# Digital_and_PS.net
KiCad netlist of a schematic drawn in Altium Designer
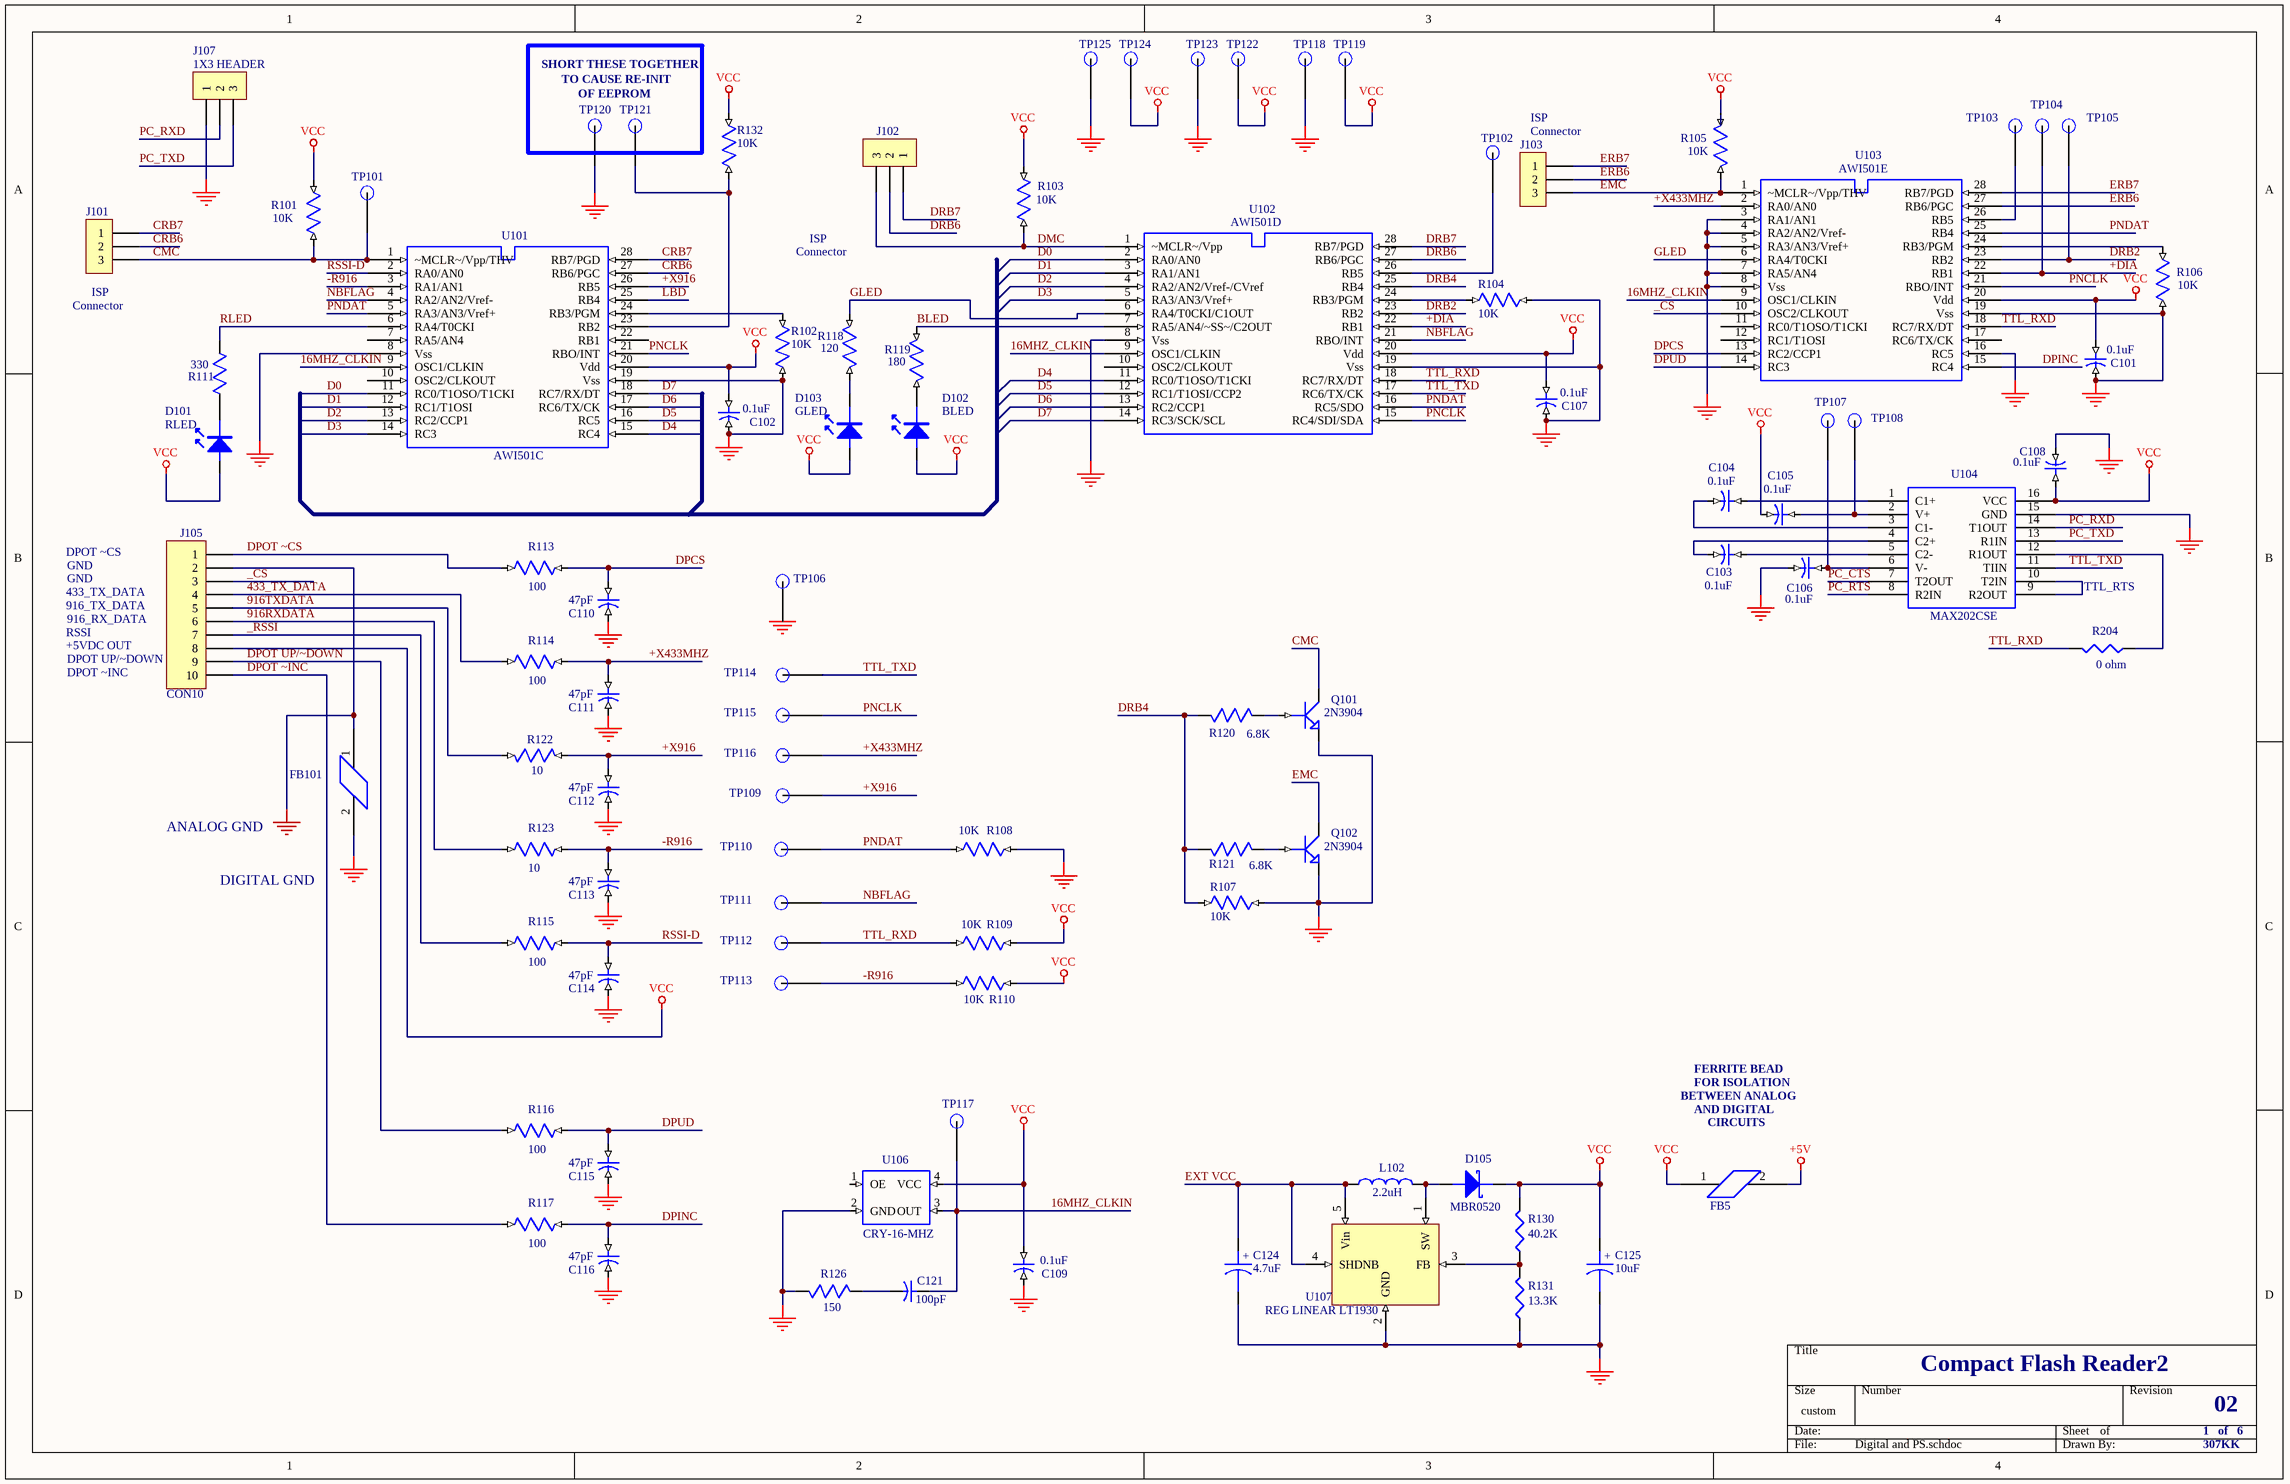
[diagram p0: Digital and PS.schdoc]

(export (version "E")
  (design (tool "Eeschema 10.0.6"))
  (components
    (comp (ref "C101") (value "0.1uF") (footprint "0603") (libsource (lib "*") (part "C_603")))
    (comp (ref "C102") (value "0.1uF") (footprint "0603") (libsource (lib "*") (part "C_603")))
    (comp (ref "C103") (value "0.1uF") (footprint "0603") (libsource (lib "") (part "C_603_1")))
    (comp (ref "C104") (value "0.1uF") (footprint "0603") (libsource (lib "") (part "C_603_1")))
    (comp (ref "C105") (value "0.1uF") (footprint "0603") (libsource (lib "") (part "C_603_1")))
    (comp (ref "C106") (value "0.1uF") (footprint "0603") (libsource (lib "") (part "C_603_1")))
    (comp (ref "C107") (value "0.1uF") (footprint "0603") (libsource (lib "*") (part "C_603")))
    (comp (ref "C108") (value "0.1uF") (footprint "0603") (libsource (lib "") (part "C_603_1")))
    (comp (ref "C109") (value "0.1uF") (footprint "0603") (libsource (lib "") (part "C_603_1")))
    (comp (ref "C110") (value "47pF") (footprint "0603") (libsource (lib "*") (part "C0603")))
    (comp (ref "C111") (value "47pF") (footprint "0603") (libsource (lib "*") (part "C0603")))
    (comp (ref "C112") (value "47pF") (footprint "0603") (libsource (lib "*") (part "C0603")))
    (comp (ref "C113") (value "47pF") (footprint "0603") (libsource (lib "*") (part "C0603")))
    (comp (ref "C114") (value "47pF") (footprint "0603") (libsource (lib "*") (part "C0603")))
    (comp (ref "C115") (value "47pF") (footprint "0603") (libsource (lib "*") (part "C0603")))
    (comp (ref "C116") (value "47pF") (footprint "0603") (libsource (lib "*") (part "C0603")))
    (comp (ref "C121") (value "100pF") (footprint "0603") (libsource (lib "*") (part "C_0603")))
    (comp (ref "C124")
      (value "4.7uF")
      (footprint "CAP A CASE")
      (description "Capacitor")
      (libsource (lib "*") (part "CAPACITOR POL"))
    )
    (comp (ref "C125")
      (value "10uF")
      (footprint "CAP A CASE")
      (description "Capacitor")
      (libsource (lib "*") (part "CAPACITOR POL"))
    )
    (comp (ref "D101") (value "RLED") (footprint "SOD123 DIODE") (libsource (lib "*") (part "LED")))
    (comp (ref "D102") (value "BLED") (footprint "SOD123 DIODE") (libsource (lib "*") (part "LED")))
    (comp (ref "D103") (value "GLED") (footprint "SOD123 DIODE") (libsource (lib "*") (part "LED")))
    (comp (ref "D105")
      (value "MBR0520")
      (footprint "SOD123")
      (description "Schottky Diode")
      (libsource (lib "*") (part "DIODE SCHOTTKY"))
    )
    (comp (ref "FB5") (value "FB") (footprint "0603") (libsource (lib "*") (part "FB_0603")))
    (comp (ref "FB101") (value "FB") (footprint "0603") (libsource (lib "*") (part "FB_0603")))
    (comp (ref "J101")
      (value "1X3 HEADER")
      (footprint "1X3 HEADER")
      (description "Connector")
      (libsource (lib "") (part "CON3_1"))
    )
    (comp (ref "J102")
      (value "1X3 HEADER")
      (footprint "1X3 HEADER")
      (description "Connector")
      (libsource (lib "*") (part "CON3"))
    )
    (comp (ref "J103")
      (value "1X3 HEADER")
      (footprint "1X3 HEADER")
      (description "Connector")
      (libsource (lib "") (part "CON3_1"))
    )
    (comp (ref "J105")
      (value "CON10")
      (footprint "1X10 HEADER SPECIAL")
      (description "Connector")
      (libsource (lib "*") (part "CON10"))
    )
    (comp (ref "J107")
      (value "1X3 HEADER")
      (footprint "1X3 HEADER")
      (description "Connector")
      (libsource (lib "") (part "CON3_2"))
    )
    (comp (ref "L102")
      (value "2.2uH")
      (footprint "COIL BOURNS SDR7030-330M")
      (libsource (lib "*") (part "INDUCTOR1"))
    )
    (comp (ref "Q101")
      (value "2N3904")
      (footprint "SOT23 TRANS")
      (description "NPN Transistor")
      (libsource (lib "*") (part "NPN1"))
    )
    (comp (ref "Q102")
      (value "2N3904")
      (footprint "SOT23 TRANS")
      (description "NPN Transistor")
      (libsource (lib "*") (part "NPN1"))
    )
    (comp (ref "R101") (value "10K") (footprint "0603") (libsource (lib "*") (part "R_603")))
    (comp (ref "R102") (value "10K") (footprint "0603") (libsource (lib "*") (part "R_603")))
    (comp (ref "R103") (value "10K") (footprint "0603") (libsource (lib "*") (part "R_603")))
    (comp (ref "R104") (value "10K") (footprint "0603") (libsource (lib "*") (part "R_603")))
    (comp (ref "R105") (value "10K") (footprint "0603") (libsource (lib "*") (part "R_603")))
    (comp (ref "R106") (value "10K") (footprint "0603") (libsource (lib "*") (part "R_603")))
    (comp (ref "R107") (value "10K") (footprint "0603") (libsource (lib "*") (part "R_603")))
    (comp (ref "R108") (value "10K") (footprint "0603") (libsource (lib "*") (part "R_603")))
    (comp (ref "R109") (value "10K") (footprint "0603") (libsource (lib "*") (part "R_603")))
    (comp (ref "R110") (value "10K") (footprint "0603") (libsource (lib "*") (part "R_603")))
    (comp (ref "R111") (value "330") (footprint "0603") (libsource (lib "*") (part "R_0603")))
    (comp (ref "R113") (value "100") (footprint "0603") (libsource (lib "*") (part "R0603")))
    (comp (ref "R114") (value "100") (footprint "0603") (libsource (lib "*") (part "R0603")))
    (comp (ref "R115") (value "100") (footprint "0603") (libsource (lib "*") (part "R0603")))
    (comp (ref "R116") (value "100") (footprint "0603") (libsource (lib "*") (part "R0603")))
    (comp (ref "R117") (value "100") (footprint "0603") (libsource (lib "*") (part "R0603")))
    (comp (ref "R118") (value "120") (footprint "0603") (libsource (lib "*") (part "R0402")))
    (comp (ref "R119") (value "180") (footprint "0603") (libsource (lib "*") (part "R0402")))
    (comp (ref "R120") (value "6.8K") (footprint "0603") (libsource (lib "*") (part "R_0603")))
    (comp (ref "R121") (value "6.8K") (footprint "0603") (libsource (lib "*") (part "R_0603")))
    (comp (ref "R122") (value "10") (footprint "0603") (libsource (lib "*") (part "R_603")))
    (comp (ref "R123") (value "10") (footprint "0603") (libsource (lib "*") (part "R0603")))
    (comp (ref "R126") (value "150") (footprint "0603") (libsource (lib "*") (part "R_0603")))
    (comp (ref "R130") (value "40.2K") (footprint "0603") (libsource (lib "*") (part "RES1")))
    (comp (ref "R131") (value "13.3K") (footprint "0603") (libsource (lib "*") (part "RES1")))
    (comp (ref "R132") (value "10K") (footprint "0603") (libsource (lib "*") (part "R_603")))
    (comp (ref "R204") (value "0 ohm") (footprint "0603") (libsource (lib "*") (part "RES1")))
    (comp (ref "TP101") (value "TP") (footprint "TEST POINT PAD") (libsource (lib "*") (part "TESTPOINT_1")))
    (comp (ref "TP102") (value "TP") (footprint "TEST POINT PAD") (libsource (lib "*") (part "TESTPOINT_1")))
    (comp (ref "TP103") (value "TP") (footprint "TEST POINT PAD") (libsource (lib "*") (part "TESTPOINT_1")))
    (comp (ref "TP104") (value "TP") (footprint "TEST POINT PAD") (libsource (lib "*") (part "TESTPOINT_1")))
    (comp (ref "TP105") (value "TP") (footprint "TEST POINT PAD") (libsource (lib "*") (part "TESTPOINT_1")))
    (comp (ref "TP106") (value "TP") (footprint "TEST POINT PAD") (libsource (lib "*") (part "TESTPOINT_1")))
    (comp (ref "TP107") (value "TP") (footprint "TEST POINT PAD") (libsource (lib "*") (part "TESTPOINT_1")))
    (comp (ref "TP108") (value "TP") (footprint "TEST POINT PAD") (libsource (lib "*") (part "TESTPOINT_1")))
    (comp (ref "TP109") (value "TP") (footprint "TEST POINT PAD") (libsource (lib "*") (part "TESTPOINT_1")))
    (comp (ref "TP110") (value "TP") (footprint "TEST POINT PAD") (libsource (lib "*") (part "TESTPOINT_1")))
    (comp (ref "TP111") (value "TP") (footprint "TEST POINT PAD") (libsource (lib "*") (part "TESTPOINT_1")))
    (comp (ref "TP112") (value "TP") (footprint "TEST POINT PAD") (libsource (lib "*") (part "TESTPOINT_1")))
    (comp (ref "TP113") (value "TP") (footprint "TEST POINT PAD") (libsource (lib "*") (part "TESTPOINT_1")))
    (comp (ref "TP114") (value "TP") (footprint "TEST POINT PAD") (libsource (lib "*") (part "TESTPOINT_1")))
    (comp (ref "TP115") (value "TP") (footprint "TEST POINT PAD") (libsource (lib "*") (part "TESTPOINT_1")))
    (comp (ref "TP116") (value "TP") (footprint "TEST POINT PAD") (libsource (lib "*") (part "TESTPOINT_1")))
    (comp (ref "TP117") (value "TP") (footprint "TEST POINT PAD") (libsource (lib "*") (part "TESTPOINT_1")))
    (comp (ref "TP118") (value "TP") (footprint "TEST POINT PAD") (libsource (lib "*") (part "TESTPOINT_1")))
    (comp (ref "TP119") (value "TP") (footprint "TEST POINT PAD") (libsource (lib "*") (part "TESTPOINT_1")))
    (comp (ref "TP120") (value "TP") (footprint "TEST POINT PAD") (libsource (lib "*") (part "TESTPOINT_1")))
    (comp (ref "TP121") (value "TP") (footprint "TEST POINT PAD") (libsource (lib "*") (part "TESTPOINT_1")))
    (comp (ref "TP122") (value "TP") (footprint "TEST POINT PAD") (libsource (lib "*") (part "TESTPOINT_1")))
    (comp (ref "TP123") (value "TP") (footprint "TEST POINT PAD") (libsource (lib "*") (part "TESTPOINT_1")))
    (comp (ref "TP124") (value "TP") (footprint "TEST POINT PAD") (libsource (lib "*") (part "TESTPOINT_1")))
    (comp (ref "TP125") (value "TP") (footprint "TEST POINT PAD") (libsource (lib "*") (part "TESTPOINT_1")))
    (comp (ref "U101") (value "AWI501C") (footprint "SSOP28") (libsource (lib "*") (part "PIC16F870")))
    (comp (ref "U102") (value "AWI501D") (footprint "SSOP28") (libsource (lib "*") (part "PIC16F876A")))
    (comp (ref "U103") (value "AWI501E") (footprint "SSOP28") (libsource (lib "*") (part "PIC16F870")))
    (comp (ref "U104") (value "MAX202CSE") (footprint "SO16") (libsource (lib "*") (part "MAX202CSE")))
    (comp (ref "U106")
      (value "CRY-16-MHZ")
      (footprint "SMT OSCILLATOR")
      (libsource (lib "*") (part "CRY-SMD-5-7"))
    )
    (comp (ref "U107")
      (value "REG LINEAR LT1930")
      (footprint "SOT23-5A")
      (libsource (lib "*") (part "REG LINEAR LT1930"))
    )
  )
  (nets
    (net (code "1") (name "+5V") (class "Default")
      (node (ref "FB5") (pin "2") (pinfunction "1_2") (pintype "passive"))
    )
    (net (code "2") (name "/+DIA") (class "Default")
      (node (ref "TP104") (pin "1") (pinfunction "TP_1") (pintype "passive"))
      (node (ref "U102") (pin "22") (pinfunction "RB1_22") (pintype "input"))
      (node (ref "U103") (pin "22") (pinfunction "RB1_22") (pintype "input"))
    )
    (net (code "3") (name "/+X433MHZ") (class "Default")
      (node (ref "C111") (pin "1") (pinfunction "A_1") (pintype "input"))
      (node (ref "R114") (pin "2") (pinfunction "B_2") (pintype "input"))
      (node (ref "TP116") (pin "1") (pinfunction "TP_1") (pintype "passive"))
      (node (ref "U103") (pin "2") (pinfunction "RA0/AN0_2") (pintype "input"))
    )
    (net (code "4") (name "/+X916") (class "Default")
      (node (ref "C112") (pin "1") (pinfunction "A_1") (pintype "input"))
      (node (ref "R122") (pin "1") (pinfunction "A_1") (pintype "input"))
      (node (ref "TP109") (pin "1") (pinfunction "TP_1") (pintype "passive"))
      (node (ref "U101") (pin "26") (pinfunction "RB5_26") (pintype "input"))
    )
    (net (code "5") (name "/-R916") (class "Default")
      (node (ref "C113") (pin "1") (pinfunction "A_1") (pintype "input"))
      (node (ref "R110") (pin "2") (pinfunction "B_2") (pintype "input"))
      (node (ref "R123") (pin "2") (pinfunction "B_2") (pintype "input"))
      (node (ref "TP113") (pin "1") (pinfunction "TP_1") (pintype "passive"))
      (node (ref "U101") (pin "3") (pinfunction "RA1/AN1_3") (pintype "input"))
    )
    (net (code "6") (name "/16MHZ_CLKIN") (class "Default")
      (node (ref "C121") (pin "1") (pinfunction "A_1") (pintype "passive"))
      (node (ref "TP117") (pin "1") (pinfunction "TP_1") (pintype "passive"))
      (node (ref "U101") (pin "9") (pinfunction "OSC1/CLKIN_9") (pintype "input"))
      (node (ref "U102") (pin "9") (pinfunction "OSC1/CLKIN_9") (pintype "input"))
      (node (ref "U103") (pin "9") (pinfunction "OSC1/CLKIN_9") (pintype "input"))
      (node (ref "U106") (pin "3") (pinfunction "OUT_3") (pintype "input"))
    )
    (net (code "7") (name "/433_TX_DATA") (class "Default")
      (node (ref "J105") (pin "4") (pinfunction "4_4") (pintype "passive"))
      (node (ref "R114") (pin "1") (pinfunction "A_1") (pintype "input"))
    )
    (net (code "8") (name "/916RXDATA") (class "Default")
      (node (ref "J105") (pin "6") (pinfunction "6_6") (pintype "passive"))
      (node (ref "R123") (pin "1") (pinfunction "A_1") (pintype "input"))
    )
    (net (code "9") (name "/916TXDATA") (class "Default")
      (node (ref "J105") (pin "5") (pinfunction "5_5") (pintype "passive"))
      (node (ref "R122") (pin "2") (pinfunction "B_2") (pintype "input"))
    )
    (net (code "10") (name "/BLED") (class "Default")
      (node (ref "R119") (pin "2") (pinfunction "B_2") (pintype "input"))
      (node (ref "U102") (pin "7") (pinfunction "RA5/AN4/~SS~/C2OUT_7") (pintype "input"))
    )
    (net (code "11") (name "/CMC") (class "Default")
      (node (ref "J101") (pin "3") (pinfunction "3_3") (pintype "passive"))
      (node (ref "Q101") (pin "C") (pinfunction "C_C") (pintype "passive"))
      (node (ref "R101") (pin "2") (pinfunction "B_2") (pintype "input"))
      (node (ref "TP101") (pin "1") (pinfunction "TP_1") (pintype "passive"))
      (node (ref "U101") (pin "1") (pinfunction "~MCLR~/Vpp/THV_1") (pintype "input"))
    )
    (net (code "12") (name "/CRB6") (class "Default")
      (node (ref "J101") (pin "2") (pinfunction "2_2") (pintype "passive"))
      (node (ref "U101") (pin "27") (pinfunction "RB6/PGC_27") (pintype "input"))
    )
    (net (code "13") (name "/CRB7") (class "Default")
      (node (ref "J101") (pin "1") (pinfunction "1_1") (pintype "passive"))
      (node (ref "U101") (pin "28") (pinfunction "RB7/PGD_28") (pintype "input"))
    )
    (net (code "14") (name "/D0") (class "Default")
      (node (ref "U101") (pin "11") (pinfunction "RC0/T1OSO/T1CKI_11") (pintype "input"))
      (node (ref "U102") (pin "2") (pinfunction "RA0/AN0_2") (pintype "input"))
    )
    (net (code "15") (name "/D1") (class "Default")
      (node (ref "U101") (pin "12") (pinfunction "RC1/T1OSI_12") (pintype "input"))
      (node (ref "U102") (pin "3") (pinfunction "RA1/AN1_3") (pintype "input"))
    )
    (net (code "16") (name "/D2") (class "Default")
      (node (ref "U101") (pin "13") (pinfunction "RC2/CCP1_13") (pintype "input"))
      (node (ref "U102") (pin "4") (pinfunction "RA2/AN2/Vref-/CVref_4") (pintype "input"))
    )
    (net (code "17") (name "/D3") (class "Default")
      (node (ref "U101") (pin "14") (pinfunction "RC3_14") (pintype "input"))
      (node (ref "U102") (pin "5") (pinfunction "RA3/AN3/Vref+_5") (pintype "input"))
    )
    (net (code "18") (name "/D4") (class "Default")
      (node (ref "U101") (pin "15") (pinfunction "RC4_15") (pintype "input"))
      (node (ref "U102") (pin "11") (pinfunction "RC0/T1OSO/T1CKI_11") (pintype "input"))
    )
    (net (code "19") (name "/D5") (class "Default")
      (node (ref "U101") (pin "16") (pinfunction "RC5_16") (pintype "input"))
      (node (ref "U102") (pin "12") (pinfunction "RC1/T1OSI/CCP2_12") (pintype "input"))
    )
    (net (code "20") (name "/D6") (class "Default")
      (node (ref "U101") (pin "17") (pinfunction "RC6/TX/CK_17") (pintype "input"))
      (node (ref "U102") (pin "13") (pinfunction "RC2/CCP1_13") (pintype "input"))
    )
    (net (code "21") (name "/D7") (class "Default")
      (node (ref "U101") (pin "18") (pinfunction "RC7/RX/DT_18") (pintype "input"))
      (node (ref "U102") (pin "14") (pinfunction "RC3/SCK/SCL_14") (pintype "input"))
    )
    (net (code "22") (name "/DMC") (class "Default")
      (node (ref "J102") (pin "3") (pinfunction "3_3") (pintype "passive"))
      (node (ref "R103") (pin "2") (pinfunction "B_2") (pintype "input"))
      (node (ref "U102") (pin "1") (pinfunction "~MCLR~/Vpp_1") (pintype "input"))
    )
    (net (code "23") (name "/DPCS") (class "Default")
      (node (ref "C110") (pin "1") (pinfunction "A_1") (pintype "input"))
      (node (ref "R113") (pin "2") (pinfunction "B_2") (pintype "input"))
      (node (ref "U103") (pin "13") (pinfunction "RC2/CCP1_13") (pintype "input"))
    )
    (net (code "24") (name "/DPINC") (class "Default")
      (node (ref "C116") (pin "1") (pinfunction "A_1") (pintype "input"))
      (node (ref "R117") (pin "2") (pinfunction "B_2") (pintype "input"))
      (node (ref "U103") (pin "15") (pinfunction "RC4_15") (pintype "input"))
    )
    (net (code "25") (name "/DPOT UP{slash}~DOWN") (class "Default")
      (node (ref "J105") (pin "9") (pinfunction "9_9") (pintype "passive"))
      (node (ref "R116") (pin "1") (pinfunction "A_1") (pintype "input"))
    )
    (net (code "26") (name "/DPOT ~CS") (class "Default")
      (node (ref "J105") (pin "1") (pinfunction "1_1") (pintype "passive"))
      (node (ref "R113") (pin "1") (pinfunction "A_1") (pintype "input"))
    )
    (net (code "27") (name "/DPOT ~INC") (class "Default")
      (node (ref "J105") (pin "10") (pinfunction "10_10") (pintype "passive"))
      (node (ref "R117") (pin "1") (pinfunction "A_1") (pintype "input"))
    )
    (net (code "28") (name "/DPUD") (class "Default")
      (node (ref "C115") (pin "1") (pinfunction "A_1") (pintype "input"))
      (node (ref "R116") (pin "2") (pinfunction "B_2") (pintype "input"))
      (node (ref "U103") (pin "14") (pinfunction "RC3_14") (pintype "input"))
    )
    (net (code "29") (name "/DRB2") (class "Default")
      (node (ref "TP105") (pin "1") (pinfunction "TP_1") (pintype "passive"))
      (node (ref "U102") (pin "23") (pinfunction "RB2_23") (pintype "input"))
      (node (ref "U103") (pin "23") (pinfunction "RB2_23") (pintype "input"))
    )
    (net (code "30") (name "/DRB4") (class "Default")
      (node (ref "R107") (pin "1") (pinfunction "A_1") (pintype "input"))
      (node (ref "R120") (pin "1") (pinfunction "A_1") (pintype "passive"))
      (node (ref "R121") (pin "1") (pinfunction "A_1") (pintype "passive"))
      (node (ref "U102") (pin "25") (pinfunction "RB4_25") (pintype "input"))
    )
    (net (code "31") (name "/DRB6") (class "Default")
      (node (ref "J102") (pin "2") (pinfunction "2_2") (pintype "passive"))
      (node (ref "U102") (pin "27") (pinfunction "RB6/PGC_27") (pintype "input"))
    )
    (net (code "32") (name "/DRB7") (class "Default")
      (node (ref "J102") (pin "1") (pinfunction "1_1") (pintype "passive"))
      (node (ref "U102") (pin "28") (pinfunction "RB7/PGD_28") (pintype "input"))
    )
    (net (code "33") (name "/EMC") (class "Default")
      (node (ref "J103") (pin "3") (pinfunction "3_3") (pintype "passive"))
      (node (ref "Q102") (pin "C") (pinfunction "C_C") (pintype "passive"))
      (node (ref "R105") (pin "2") (pinfunction "B_2") (pintype "input"))
      (node (ref "U103") (pin "1") (pinfunction "~MCLR~/Vpp/THV_1") (pintype "input"))
    )
    (net (code "34") (name "/ERB6") (class "Default")
      (node (ref "J103") (pin "2") (pinfunction "2_2") (pintype "passive"))
      (node (ref "U103") (pin "27") (pinfunction "RB6/PGC_27") (pintype "input"))
    )
    (net (code "35") (name "/ERB7") (class "Default")
      (node (ref "J103") (pin "1") (pinfunction "1_1") (pintype "passive"))
      (node (ref "U103") (pin "28") (pinfunction "RB7/PGD_28") (pintype "input"))
    )
    (net (code "36") (name "/EXT VCC") (class "Default")
      (node (ref "C124") (pin "1") (pinfunction "1_1") (pintype "passive"))
      (node (ref "L102") (pin "1") (pinfunction "1_1") (pintype "passive"))
      (node (ref "U107") (pin "4") (pinfunction "SHDNB_4") (pintype "input"))
      (node (ref "U107") (pin "5") (pinfunction "Vin_5") (pintype "input"))
    )
    (net (code "37") (name "/GLED") (class "Default")
      (node (ref "R118") (pin "2") (pinfunction "B_2") (pintype "input"))
      (node (ref "U102") (pin "6") (pinfunction "RA4/T0CKI/C1OUT_6") (pintype "input"))
      (node (ref "U103") (pin "6") (pinfunction "RA4/T0CKI_6") (pintype "input"))
    )
    (net (code "38") (name "/LBD") (class "Default")
      (node (ref "U101") (pin "25") (pinfunction "RB4_25") (pintype "input"))
    )
    (net (code "39") (name "/NBFLAG") (class "Default")
      (node (ref "TP111") (pin "1") (pinfunction "TP_1") (pintype "passive"))
      (node (ref "U101") (pin "4") (pinfunction "RA2/AN2/Vref-_4") (pintype "input"))
      (node (ref "U102") (pin "21") (pinfunction "RBO/INT_21") (pintype "input"))
    )
    (net (code "40") (name "/PC_CTS") (class "Default")
      (node (ref "U104") (pin "7") (pinfunction "T2OUT_7") (pintype "passive"))
    )
    (net (code "41") (name "/PC_RTS") (class "Default")
      (node (ref "U104") (pin "8") (pinfunction "R2IN_8") (pintype "passive"))
    )
    (net (code "42") (name "/PC_RXD") (class "Default")
      (node (ref "J107") (pin "2") (pinfunction "2_2") (pintype "passive"))
      (node (ref "U104") (pin "14") (pinfunction "T1OUT_14") (pintype "passive"))
    )
    (net (code "43") (name "/PC_TXD") (class "Default")
      (node (ref "J107") (pin "3") (pinfunction "3_3") (pintype "passive"))
      (node (ref "U104") (pin "13") (pinfunction "R1IN_13") (pintype "passive"))
    )
    (net (code "44") (name "/PNCLK") (class "Default")
      (node (ref "TP115") (pin "1") (pinfunction "TP_1") (pintype "passive"))
      (node (ref "U101") (pin "21") (pinfunction "RBO/INT_21") (pintype "input"))
      (node (ref "U102") (pin "15") (pinfunction "RC4/SDI/SDA_15") (pintype "input"))
      (node (ref "U103") (pin "21") (pinfunction "RBO/INT_21") (pintype "input"))
    )
    (net (code "45") (name "/PNDAT") (class "Default")
      (node (ref "R108") (pin "2") (pinfunction "B_2") (pintype "input"))
      (node (ref "TP110") (pin "1") (pinfunction "TP_1") (pintype "passive"))
      (node (ref "U101") (pin "5") (pinfunction "RA3/AN3/Vref+_5") (pintype "input"))
      (node (ref "U102") (pin "16") (pinfunction "RC5/SDO_16") (pintype "input"))
      (node (ref "U103") (pin "25") (pinfunction "RB4_25") (pintype "input"))
    )
    (net (code "46") (name "/RLED") (class "Default")
      (node (ref "R111") (pin "2") (pinfunction "B_2") (pintype "passive"))
      (node (ref "U101") (pin "6") (pinfunction "RA4/T0CKI_6") (pintype "input"))
    )
    (net (code "47") (name "/RSSI-D") (class "Default")
      (node (ref "C114") (pin "1") (pinfunction "A_1") (pintype "input"))
      (node (ref "R115") (pin "2") (pinfunction "B_2") (pintype "input"))
      (node (ref "U101") (pin "2") (pinfunction "RA0/AN0_2") (pintype "input"))
    )
    (net (code "48") (name "/TTL_RXD") (class "Default")
      (node (ref "R109") (pin "2") (pinfunction "B_2") (pintype "input"))
      (node (ref "R204") (pin "2") (pinfunction "2_2") (pintype "passive"))
      (node (ref "TP112") (pin "1") (pinfunction "TP_1") (pintype "passive"))
      (node (ref "U102") (pin "18") (pinfunction "RC7/RX/DT_18") (pintype "input"))
      (node (ref "U103") (pin "18") (pinfunction "RC7/RX/DT_18") (pintype "input"))
    )
    (net (code "49") (name "/TTL_TXD") (class "Default")
      (node (ref "TP114") (pin "1") (pinfunction "TP_1") (pintype "passive"))
      (node (ref "U102") (pin "17") (pinfunction "RC6/TX/CK_17") (pintype "input"))
      (node (ref "U104") (pin "11") (pinfunction "TIIN_11") (pintype "passive"))
    )
    (net (code "50") (name "/_CS") (class "Default")
      (node (ref "J105") (pin "3") (pinfunction "3_3") (pintype "passive"))
      (node (ref "U103") (pin "10") (pinfunction "OSC2/CLKOUT_10") (pintype "input"))
    )
    (net (code "51") (name "/_RSSI") (class "Default")
      (node (ref "J105") (pin "7") (pinfunction "7_7") (pintype "passive"))
      (node (ref "R115") (pin "1") (pinfunction "A_1") (pintype "input"))
    )
    (net (code "52") (name "GND_COM") (class "Default")
      (node (ref "C101") (pin "2") (pinfunction "B_2") (pintype "input"))
      (node (ref "C102") (pin "2") (pinfunction "B_2") (pintype "input"))
      (node (ref "C106") (pin "2") (pinfunction "B_2") (pintype "input"))
      (node (ref "C107") (pin "2") (pinfunction "B_2") (pintype "input"))
      (node (ref "C108") (pin "2") (pinfunction "B_2") (pintype "input"))
      (node (ref "C109") (pin "2") (pinfunction "B_2") (pintype "input"))
      (node (ref "C110") (pin "2") (pinfunction "B_2") (pintype "input"))
      (node (ref "C111") (pin "2") (pinfunction "B_2") (pintype "input"))
      (node (ref "C112") (pin "2") (pinfunction "B_2") (pintype "input"))
      (node (ref "C113") (pin "2") (pinfunction "B_2") (pintype "input"))
      (node (ref "C114") (pin "2") (pinfunction "B_2") (pintype "input"))
      (node (ref "C115") (pin "2") (pinfunction "B_2") (pintype "input"))
      (node (ref "C116") (pin "2") (pinfunction "B_2") (pintype "input"))
      (node (ref "C124") (pin "2") (pinfunction "2_2") (pintype "passive"))
      (node (ref "C125") (pin "2") (pinfunction "2_2") (pintype "passive"))
      (node (ref "FB101") (pin "2") (pinfunction "1_2") (pintype "passive"))
      (node (ref "J107") (pin "1") (pinfunction "1_1") (pintype "passive"))
      (node (ref "Q101") (pin "E") (pinfunction "E_E") (pintype "passive"))
      (node (ref "Q102") (pin "E") (pinfunction "E_E") (pintype "passive"))
      (node (ref "R102") (pin "2") (pinfunction "B_2") (pintype "input"))
      (node (ref "R104") (pin "1") (pinfunction "A_1") (pintype "input"))
      (node (ref "R106") (pin "2") (pinfunction "B_2") (pintype "input"))
      (node (ref "R107") (pin "2") (pinfunction "B_2") (pintype "input"))
      (node (ref "R108") (pin "1") (pinfunction "A_1") (pintype "input"))
      (node (ref "R126") (pin "2") (pinfunction "B_2") (pintype "passive"))
      (node (ref "R131") (pin "1") (pinfunction "1_1") (pintype "passive"))
      (node (ref "TP106") (pin "1") (pinfunction "TP_1") (pintype "passive"))
      (node (ref "TP118") (pin "1") (pinfunction "TP_1") (pintype "passive"))
      (node (ref "TP120") (pin "1") (pinfunction "TP_1") (pintype "passive"))
      (node (ref "TP123") (pin "1") (pinfunction "TP_1") (pintype "passive"))
      (node (ref "TP125") (pin "1") (pinfunction "TP_1") (pintype "passive"))
      (node (ref "U101") (pin "19") (pinfunction "Vss_19") (pintype "input"))
      (node (ref "U101") (pin "8") (pinfunction "Vss_8") (pintype "input"))
      (node (ref "U102") (pin "19") (pinfunction "Vss_19") (pintype "input"))
      (node (ref "U102") (pin "8") (pinfunction "Vss_8") (pintype "input"))
      (node (ref "U103") (pin "16") (pinfunction "RC5_16") (pintype "input"))
      (node (ref "U103") (pin "19") (pinfunction "Vss_19") (pintype "input"))
      (node (ref "U103") (pin "3") (pinfunction "RA1/AN1_3") (pintype "input"))
      (node (ref "U103") (pin "4") (pinfunction "RA2/AN2/Vref-_4") (pintype "input"))
      (node (ref "U103") (pin "5") (pinfunction "RA3/AN3/Vref+_5") (pintype "input"))
      (node (ref "U103") (pin "7") (pinfunction "RA5/AN4_7") (pintype "input"))
      (node (ref "U103") (pin "8") (pinfunction "Vss_8") (pintype "input"))
      (node (ref "U104") (pin "15") (pinfunction "GND_15") (pintype "passive"))
      (node (ref "U106") (pin "2") (pinfunction "GND_2") (pintype "input"))
      (node (ref "U107") (pin "2") (pinfunction "GND_2") (pintype "input"))
    )
    (net (code "53") (name "GND_SIGNAL") (class "Default")
      (node (ref "FB101") (pin "1") (pinfunction "2_1") (pintype "passive"))
      (node (ref "J105") (pin "2") (pinfunction "2_2") (pintype "passive"))
    )
    (net (code "54") (name "Net-(C103-A)") (class "Default")
      (node (ref "C103") (pin "1") (pinfunction "A_1") (pintype "input"))
      (node (ref "U104") (pin "5") (pinfunction "C2-_5") (pintype "passive"))
    )
    (net (code "55") (name "Net-(C103-B)") (class "Default")
      (node (ref "C103") (pin "2") (pinfunction "B_2") (pintype "input"))
      (node (ref "U104") (pin "4") (pinfunction "C2+_4") (pintype "passive"))
    )
    (net (code "56") (name "Net-(C104-A)") (class "Default")
      (node (ref "C104") (pin "1") (pinfunction "A_1") (pintype "input"))
      (node (ref "U104") (pin "1") (pinfunction "C1+_1") (pintype "passive"))
    )
    (net (code "57") (name "Net-(C104-B)") (class "Default")
      (node (ref "C104") (pin "2") (pinfunction "B_2") (pintype "input"))
      (node (ref "U104") (pin "3") (pinfunction "C1-_3") (pintype "passive"))
    )
    (net (code "58") (name "Net-(C105-A)") (class "Default")
      (node (ref "C105") (pin "1") (pinfunction "A_1") (pintype "input"))
      (node (ref "TP108") (pin "1") (pinfunction "TP_1") (pintype "passive"))
      (node (ref "U104") (pin "2") (pinfunction "V+_2") (pintype "passive"))
    )
    (net (code "59") (name "Net-(C106-A)") (class "Default")
      (node (ref "C106") (pin "1") (pinfunction "A_1") (pintype "input"))
      (node (ref "TP107") (pin "1") (pinfunction "TP_1") (pintype "passive"))
      (node (ref "U104") (pin "6") (pinfunction "V-_6") (pintype "passive"))
    )
    (net (code "60") (name "Net-(C121-B)") (class "Default")
      (node (ref "C121") (pin "2") (pinfunction "B_2") (pintype "passive"))
      (node (ref "R126") (pin "1") (pinfunction "A_1") (pintype "passive"))
    )
    (net (code "61") (name "Net-(R102-A)") (class "Default")
      (node (ref "R102") (pin "1") (pinfunction "A_1") (pintype "input"))
      (node (ref "U101") (pin "24") (pinfunction "RB3/PGM_24") (pintype "input"))
    )
    (net (code "62") (name "Net-(R104-B)") (class "Default")
      (node (ref "R104") (pin "2") (pinfunction "B_2") (pintype "input"))
      (node (ref "U102") (pin "24") (pinfunction "RB3/PGM_24") (pintype "input"))
    )
    (net (code "63") (name "Net-(R106-A)") (class "Default")
      (node (ref "R106") (pin "1") (pinfunction "A_1") (pintype "input"))
      (node (ref "U103") (pin "24") (pinfunction "RB3/PGM_24") (pintype "input"))
    )
    (net (code "64") (name "Net-(R111-A)") (class "Default")
      (node (ref "D101") (pin "K") (pinfunction "K_K") (pintype "passive"))
      (node (ref "R111") (pin "1") (pinfunction "A_1") (pintype "passive"))
    )
    (net (code "65") (name "Net-(R118-A)") (class "Default")
      (node (ref "D103") (pin "K") (pinfunction "K_K") (pintype "passive"))
      (node (ref "R118") (pin "1") (pinfunction "A_1") (pintype "input"))
    )
    (net (code "66") (name "Net-(R119-A)") (class "Default")
      (node (ref "D102") (pin "K") (pinfunction "K_K") (pintype "passive"))
      (node (ref "R119") (pin "1") (pinfunction "A_1") (pintype "input"))
    )
    (net (code "67") (name "Net-(R120-B)") (class "Default")
      (node (ref "Q101") (pin "B") (pinfunction "B_B") (pintype "input"))
      (node (ref "R120") (pin "2") (pinfunction "B_2") (pintype "passive"))
    )
    (net (code "68") (name "Net-(R121-B)") (class "Default")
      (node (ref "Q102") (pin "B") (pinfunction "B_B") (pintype "input"))
      (node (ref "R121") (pin "2") (pinfunction "B_2") (pintype "passive"))
    )
    (net (code "69") (name "Net-(R132-B)") (class "Default")
      (node (ref "R132") (pin "2") (pinfunction "B_2") (pintype "input"))
      (node (ref "TP121") (pin "1") (pinfunction "TP_1") (pintype "passive"))
      (node (ref "U101") (pin "23") (pinfunction "RB2_23") (pintype "input"))
    )
    (net (code "70") (name "Net-(TP102-TP)") (class "Default")
      (node (ref "TP102") (pin "1") (pinfunction "TP_1") (pintype "passive"))
      (node (ref "U102") (pin "26") (pinfunction "RB5_26") (pintype "input"))
    )
    (net (code "71") (name "Net-(TP103-TP)") (class "Default")
      (node (ref "TP103") (pin "1") (pinfunction "TP_1") (pintype "passive"))
      (node (ref "U103") (pin "26") (pinfunction "RB5_26") (pintype "input"))
    )
    (net (code "72") (name "Net-(U104-R1OUT)") (class "Default")
      (node (ref "R204") (pin "1") (pinfunction "1_1") (pintype "passive"))
      (node (ref "U104") (pin "12") (pinfunction "R1OUT_12") (pintype "passive"))
    )
    (net (code "73") (name "Net-(U104-R2OUT)") (class "Default")
      (node (ref "U104") (pin "10") (pinfunction "T2IN_10") (pintype "passive"))
      (node (ref "U104") (pin "9") (pinfunction "R2OUT_9") (pintype "passive"))
    )
    (net (code "74") (name "Net-(U107-FB)") (class "Default")
      (node (ref "R130") (pin "1") (pinfunction "1_1") (pintype "passive"))
      (node (ref "R131") (pin "2") (pinfunction "2_2") (pintype "passive"))
      (node (ref "U107") (pin "3") (pinfunction "FB_3") (pintype "input"))
    )
    (net (code "75") (name "Net-(U107-SW)") (class "Default")
      (node (ref "D105") (pin "A") (pinfunction "A_A") (pintype "passive"))
      (node (ref "L102") (pin "2") (pinfunction "2_2") (pintype "passive"))
      (node (ref "U107") (pin "1") (pinfunction "SW_1") (pintype "input"))
    )
    (net (code "76") (name "VCC") (class "Default")
      (node (ref "C101") (pin "1") (pinfunction "A_1") (pintype "input"))
      (node (ref "C102") (pin "1") (pinfunction "A_1") (pintype "input"))
      (node (ref "C105") (pin "2") (pinfunction "B_2") (pintype "input"))
      (node (ref "C107") (pin "1") (pinfunction "A_1") (pintype "input"))
      (node (ref "C108") (pin "1") (pinfunction "A_1") (pintype "input"))
      (node (ref "C109") (pin "1") (pinfunction "A_1") (pintype "input"))
      (node (ref "C125") (pin "1") (pinfunction "1_1") (pintype "passive"))
      (node (ref "D101") (pin "A") (pinfunction "A_A") (pintype "passive"))
      (node (ref "D102") (pin "A") (pinfunction "A_A") (pintype "passive"))
      (node (ref "D103") (pin "A") (pinfunction "A_A") (pintype "passive"))
      (node (ref "D105") (pin "K") (pinfunction "K_K") (pintype "passive"))
      (node (ref "FB5") (pin "1") (pinfunction "2_1") (pintype "passive"))
      (node (ref "J105") (pin "8") (pinfunction "8_8") (pintype "passive"))
      (node (ref "R101") (pin "1") (pinfunction "A_1") (pintype "input"))
      (node (ref "R103") (pin "1") (pinfunction "A_1") (pintype "input"))
      (node (ref "R105") (pin "1") (pinfunction "A_1") (pintype "input"))
      (node (ref "R109") (pin "1") (pinfunction "A_1") (pintype "input"))
      (node (ref "R110") (pin "1") (pinfunction "A_1") (pintype "input"))
      (node (ref "R130") (pin "2") (pinfunction "2_2") (pintype "passive"))
      (node (ref "R132") (pin "1") (pinfunction "A_1") (pintype "input"))
      (node (ref "TP119") (pin "1") (pinfunction "TP_1") (pintype "passive"))
      (node (ref "TP122") (pin "1") (pinfunction "TP_1") (pintype "passive"))
      (node (ref "TP124") (pin "1") (pinfunction "TP_1") (pintype "passive"))
      (node (ref "U101") (pin "20") (pinfunction "Vdd_20") (pintype "input"))
      (node (ref "U102") (pin "20") (pinfunction "Vdd_20") (pintype "input"))
      (node (ref "U103") (pin "20") (pinfunction "Vdd_20") (pintype "input"))
      (node (ref "U104") (pin "16") (pinfunction "VCC_16") (pintype "passive"))
      (node (ref "U106") (pin "4") (pinfunction "VCC_4") (pintype "input"))
    )
    (net (code "77") (name "unconnected-(U101-OSC2{slash}CLKOUT-Pad10)") (class "Default")
      (node (ref "U101") (pin "10") (pinfunction "OSC2/CLKOUT_10") (pintype "input"))
    )
    (net (code "78") (name "unconnected-(U101-RA5{slash}AN4-Pad7)") (class "Default")
      (node (ref "U101") (pin "7") (pinfunction "RA5/AN4_7") (pintype "input"))
    )
    (net (code "79") (name "unconnected-(U101-RB1-Pad22)") (class "Default")
      (node (ref "U101") (pin "22") (pinfunction "RB1_22") (pintype "input"))
    )
    (net (code "80") (name "unconnected-(U102-OSC2{slash}CLKOUT-Pad10)") (class "Default")
      (node (ref "U102") (pin "10") (pinfunction "OSC2/CLKOUT_10") (pintype "input"))
    )
    (net (code "81") (name "unconnected-(U103-RC0{slash}T1OSO{slash}T1CKI-Pad11)") (class "Default")
      (node (ref "U103") (pin "11") (pinfunction "RC0/T1OSO/T1CKI_11") (pintype "input"))
    )
    (net (code "82") (name "unconnected-(U103-RC1{slash}T1OSI-Pad12)") (class "Default")
      (node (ref "U103") (pin "12") (pinfunction "RC1/T1OSI_12") (pintype "input"))
    )
    (net (code "83") (name "unconnected-(U103-RC6{slash}TX{slash}CK-Pad17)") (class "Default")
      (node (ref "U103") (pin "17") (pinfunction "RC6/TX/CK_17") (pintype "input"))
    )
    (net (code "84") (name "unconnected-(U106-OE-Pad1)") (class "Default")
      (node (ref "U106") (pin "1") (pinfunction "OE_1") (pintype "input"))
    )
  )
)
